# Schematic.net
KiCad netlist of a schematic drawn in EasyEDA
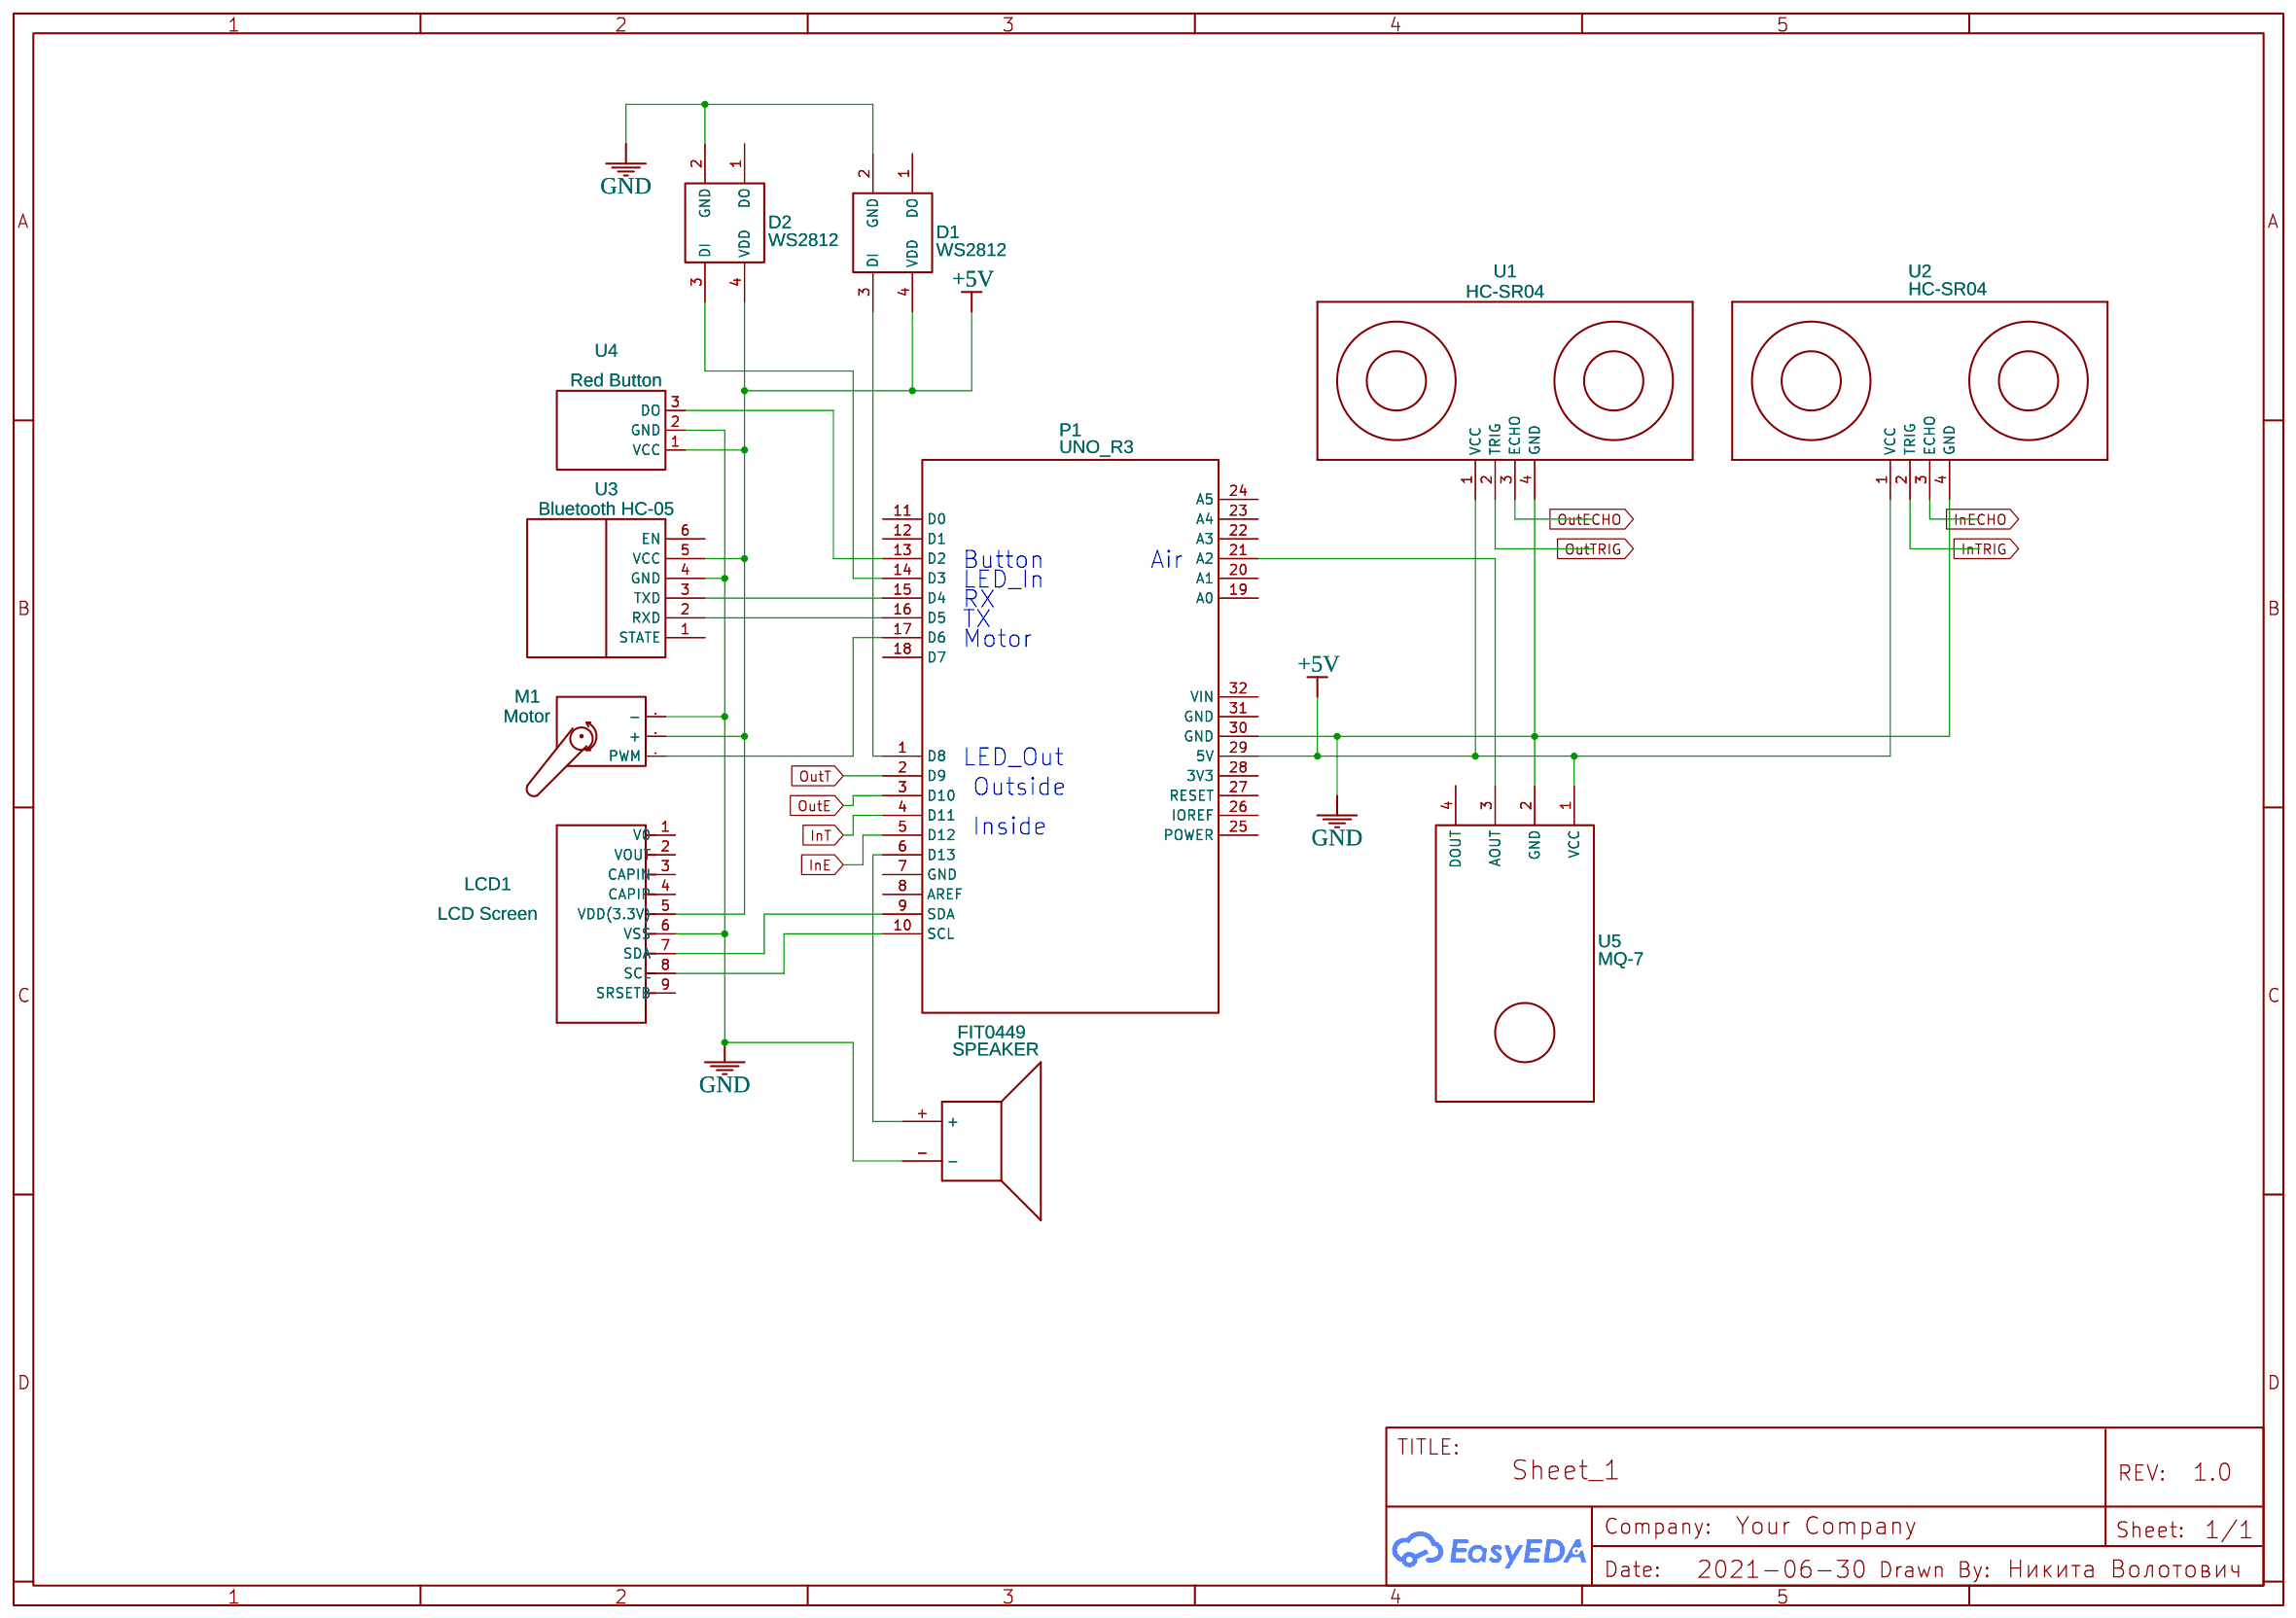
[diagram p0: schematic sheet]

(export (version "E")
  (design (tool "Eeschema 10.0.6"))
  (components
    (comp (ref "D1")
      (value "WS2812")
      (fields (field (name "BOM_Supplier Part") "WS2812B-2020"))
      (libsource (lib "") (part "WS2812"))
    )
    (comp (ref "D2")
      (value "WS2812")
      (fields (field (name "BOM_Supplier Part") "WS2812B-2020"))
      (libsource (lib "") (part "WS2812"))
    )
    (comp (ref "FIT0449") (value "SPEAKER") (libsource (lib "") (part "SPEAKER")))
    (comp (ref "LCD1")
      (value "LCD Screen")
      (fields (field (name "BOM_Manufacturer Part") "12 LCD Breadout"))
      (libsource (lib "") (part "12 LCD Breadout"))
    )
    (comp (ref "M1") (value "Motor") (libsource (lib "") (part "Servo")))
    (comp (ref "P1") (value "UNO_R3") (libsource (lib "") (part "UNO_R3")))
    (comp (ref "U1") (value "HC-SR04") (libsource (lib "") (part "HC-SR04")))
    (comp (ref "U2") (value "HC-SR04") (libsource (lib "") (part "HC-SR04")))
    (comp (ref "U3") (value "Bluetooth HC-05") (libsource (lib "") (part "HC-05")))
    (comp (ref "U4") (value "Red Button") (libsource (lib "") (part "Button")))
    (comp (ref "U5") (value "MQ-7") (libsource (lib "") (part "MQ-7")))
  )
  (nets
    (net (code "1") (name "+5V") (class "Default")
      (node (ref "D1") (pin "4") (pinfunction "VDD_4") (pintype "unspecified"))
      (node (ref "D2") (pin "4") (pinfunction "VDD_4") (pintype "unspecified"))
      (node (ref "LCD1") (pin "5") (pinfunction "VDD(3.3V)_5") (pintype "input"))
      (node (ref "M1") (pin "2") (pinfunction "+_2") (pintype "unspecified"))
      (node (ref "P1") (pin "29") (pinfunction "5V_29") (pintype "unspecified"))
      (node (ref "U1") (pin "1") (pinfunction "VCC_1") (pintype "passive"))
      (node (ref "U2") (pin "1") (pinfunction "VCC_1") (pintype "passive"))
      (node (ref "U3") (pin "5") (pinfunction "VCC_5") (pintype "unspecified"))
      (node (ref "U4") (pin "1") (pinfunction "VCC_1") (pintype "bidirectional"))
      (node (ref "U5") (pin "1") (pinfunction "VCC_1") (pintype "unspecified"))
    )
    (net (code "2") (name "GND") (class "Default")
      (node (ref "D1") (pin "2") (pinfunction "GND_2") (pintype "unspecified"))
      (node (ref "D2") (pin "2") (pinfunction "GND_2") (pintype "unspecified"))
      (node (ref "FIT0449") (pin "-") (pinfunction "-_-") (pintype "unspecified"))
      (node (ref "LCD1") (pin "6") (pinfunction "VSS_6") (pintype "input"))
      (node (ref "M1") (pin "3") (pinfunction "-_3") (pintype "unspecified"))
      (node (ref "P1") (pin "30") (pinfunction "GND_30") (pintype "unspecified"))
      (node (ref "U1") (pin "4") (pinfunction "GND_4") (pintype "passive"))
      (node (ref "U2") (pin "4") (pinfunction "GND_4") (pintype "passive"))
      (node (ref "U3") (pin "4") (pinfunction "GND_4") (pintype "unspecified"))
      (node (ref "U4") (pin "2") (pinfunction "GND_2") (pintype "bidirectional"))
      (node (ref "U5") (pin "2") (pinfunction "GND_2") (pintype "unspecified"))
    )
    (net (code "3") (name "InE") (class "Default")
      (node (ref "P1") (pin "5") (pinfunction "D12_5") (pintype "unspecified"))
    )
    (net (code "5") (name "InT") (class "Default")
      (node (ref "P1") (pin "4") (pinfunction "D11_4") (pintype "unspecified"))
    )
    (net (code "7") (name "Net-(D1-DI)") (class "Default")
      (node (ref "D1") (pin "3") (pinfunction "DI_3") (pintype "unspecified"))
      (node (ref "P1") (pin "1") (pinfunction "D8_1") (pintype "unspecified"))
    )
    (net (code "8") (name "Net-(D2-DI)") (class "Default")
      (node (ref "D2") (pin "3") (pinfunction "DI_3") (pintype "unspecified"))
      (node (ref "P1") (pin "14") (pinfunction "D3_14") (pintype "unspecified"))
    )
    (net (code "9") (name "Net-(LCD1-SCL)") (class "Default")
      (node (ref "LCD1") (pin "8") (pinfunction "SCL_8") (pintype "input"))
      (node (ref "P1") (pin "10") (pinfunction "SCL_10") (pintype "unspecified"))
    )
    (net (code "10") (name "Net-(LCD1-SDA)") (class "Default")
      (node (ref "LCD1") (pin "7") (pinfunction "SDA_7") (pintype "input"))
      (node (ref "P1") (pin "9") (pinfunction "SDA_9") (pintype "unspecified"))
    )
    (net (code "11") (name "Net-(M1-PWM)") (class "Default")
      (node (ref "M1") (pin "1") (pinfunction "PWM_1") (pintype "unspecified"))
      (node (ref "P1") (pin "17") (pinfunction "D6_17") (pintype "unspecified"))
    )
    (net (code "12") (name "Net-(P1-A2)") (class "Default")
      (node (ref "P1") (pin "21") (pinfunction "A2_21") (pintype "unspecified"))
      (node (ref "U5") (pin "3") (pinfunction "AOUT_3") (pintype "unspecified"))
    )
    (net (code "13") (name "Net-(P1-D2)") (class "Default")
      (node (ref "P1") (pin "13") (pinfunction "D2_13") (pintype "unspecified"))
      (node (ref "U4") (pin "3") (pinfunction "DO_3") (pintype "output"))
    )
    (net (code "14") (name "Net-(P1-D4)") (class "Default")
      (node (ref "P1") (pin "15") (pinfunction "D4_15") (pintype "unspecified"))
      (node (ref "U3") (pin "3") (pinfunction "TXD_3") (pintype "unspecified"))
    )
    (net (code "15") (name "Net-(P1-D5)") (class "Default")
      (node (ref "P1") (pin "16") (pinfunction "D5_16") (pintype "unspecified"))
      (node (ref "U3") (pin "2") (pinfunction "RXD_2") (pintype "unspecified"))
    )
    (net (code "16") (name "Net-(P1-D13)") (class "Default")
      (node (ref "FIT0449") (pin "+") (pinfunction "+_+") (pintype "unspecified"))
      (node (ref "P1") (pin "6") (pinfunction "D13_6") (pintype "unspecified"))
    )
    (net (code "17") (name "OutE") (class "Default")
      (node (ref "P1") (pin "3") (pinfunction "D10_3") (pintype "unspecified"))
    )
    (net (code "19") (name "OutT") (class "Default")
      (node (ref "P1") (pin "2") (pinfunction "D9_2") (pintype "unspecified"))
    )
    (net (code "21") (name "unconnected-(D1-DO-Pad1)") (class "Default")
      (node (ref "D1") (pin "1") (pinfunction "DO_1") (pintype "unspecified"))
    )
    (net (code "22") (name "unconnected-(D2-DO-Pad1)") (class "Default")
      (node (ref "D2") (pin "1") (pinfunction "DO_1") (pintype "unspecified"))
    )
    (net (code "23") (name "unconnected-(LCD1-CAPIN-Pad3)") (class "Default")
      (node (ref "LCD1") (pin "3") (pinfunction "CAPIN_3") (pintype "unspecified"))
    )
    (net (code "24") (name "unconnected-(LCD1-CAPIP-Pad4)") (class "Default")
      (node (ref "LCD1") (pin "4") (pinfunction "CAPIP_4") (pintype "unspecified"))
    )
    (net (code "25") (name "unconnected-(LCD1-SRSETB-Pad9)") (class "Default")
      (node (ref "LCD1") (pin "9") (pinfunction "SRSETB_9") (pintype "input"))
    )
    (net (code "26") (name "unconnected-(LCD1-V0-Pad1)") (class "Default")
      (node (ref "LCD1") (pin "1") (pinfunction "V0_1") (pintype "unspecified"))
    )
    (net (code "27") (name "unconnected-(LCD1-VOUT-Pad2)") (class "Default")
      (node (ref "LCD1") (pin "2") (pinfunction "VOUT_2") (pintype "unspecified"))
    )
    (net (code "28") (name "unconnected-(P1-3V3-Pad28)") (class "Default")
      (node (ref "P1") (pin "28") (pinfunction "3V3_28") (pintype "unspecified"))
    )
    (net (code "29") (name "unconnected-(P1-A0-Pad19)") (class "Default")
      (node (ref "P1") (pin "19") (pinfunction "A0_19") (pintype "unspecified"))
    )
    (net (code "30") (name "unconnected-(P1-A1-Pad20)") (class "Default")
      (node (ref "P1") (pin "20") (pinfunction "A1_20") (pintype "unspecified"))
    )
    (net (code "31") (name "unconnected-(P1-A3-Pad22)") (class "Default")
      (node (ref "P1") (pin "22") (pinfunction "A3_22") (pintype "unspecified"))
    )
    (net (code "32") (name "unconnected-(P1-A4-Pad23)") (class "Default")
      (node (ref "P1") (pin "23") (pinfunction "A4_23") (pintype "unspecified"))
    )
    (net (code "33") (name "unconnected-(P1-A5-Pad24)") (class "Default")
      (node (ref "P1") (pin "24") (pinfunction "A5_24") (pintype "unspecified"))
    )
    (net (code "34") (name "unconnected-(P1-AREF-Pad8)") (class "Default")
      (node (ref "P1") (pin "8") (pinfunction "AREF_8") (pintype "unspecified"))
    )
    (net (code "35") (name "unconnected-(P1-D0-Pad11)") (class "Default")
      (node (ref "P1") (pin "11") (pinfunction "D0_11") (pintype "unspecified"))
    )
    (net (code "36") (name "unconnected-(P1-D1-Pad12)") (class "Default")
      (node (ref "P1") (pin "12") (pinfunction "D1_12") (pintype "unspecified"))
    )
    (net (code "37") (name "unconnected-(P1-D7-Pad18)") (class "Default")
      (node (ref "P1") (pin "18") (pinfunction "D7_18") (pintype "unspecified"))
    )
    (net (code "38") (name "unconnected-(P1-GND-Pad7)") (class "Default")
      (node (ref "P1") (pin "7") (pinfunction "GND_7") (pintype "unspecified"))
    )
    (net (code "39") (name "unconnected-(P1-GND-Pad31)") (class "Default")
      (node (ref "P1") (pin "31") (pinfunction "GND_31") (pintype "unspecified"))
    )
    (net (code "40") (name "unconnected-(P1-IOREF-Pad26)") (class "Default")
      (node (ref "P1") (pin "26") (pinfunction "IOREF_26") (pintype "unspecified"))
    )
    (net (code "41") (name "unconnected-(P1-POWER-Pad25)") (class "Default")
      (node (ref "P1") (pin "25") (pinfunction "POWER_25") (pintype "unspecified"))
    )
    (net (code "42") (name "unconnected-(P1-RESET-Pad27)") (class "Default")
      (node (ref "P1") (pin "27") (pinfunction "RESET_27") (pintype "unspecified"))
    )
    (net (code "43") (name "unconnected-(P1-VIN-Pad32)") (class "Default")
      (node (ref "P1") (pin "32") (pinfunction "VIN_32") (pintype "unspecified"))
    )
    (net (code "44") (name "unconnected-(U1-ECHO-Pad3)") (class "Default")
      (node (ref "U1") (pin "3") (pinfunction "ECHO_3") (pintype "output"))
    )
    (net (code "45") (name "unconnected-(U1-TRIG-Pad2)") (class "Default")
      (node (ref "U1") (pin "2") (pinfunction "TRIG_2") (pintype "input"))
    )
    (net (code "46") (name "unconnected-(U2-ECHO-Pad3)") (class "Default")
      (node (ref "U2") (pin "3") (pinfunction "ECHO_3") (pintype "output"))
    )
    (net (code "47") (name "unconnected-(U2-TRIG-Pad2)") (class "Default")
      (node (ref "U2") (pin "2") (pinfunction "TRIG_2") (pintype "input"))
    )
    (net (code "48") (name "unconnected-(U3-EN-Pad6)") (class "Default")
      (node (ref "U3") (pin "6") (pinfunction "EN_6") (pintype "unspecified"))
    )
    (net (code "49") (name "unconnected-(U3-STATE-Pad1)") (class "Default")
      (node (ref "U3") (pin "1") (pinfunction "STATE_1") (pintype "unspecified"))
    )
    (net (code "50") (name "unconnected-(U5-DOUT-Pad4)") (class "Default")
      (node (ref "U5") (pin "4") (pinfunction "DOUT_4") (pintype "unspecified"))
    )
  )
)
